# SHDN-CURRENT-S06-V00-5kWSimulation.net
KiCad netlist of a schematic drawn in Altium Designer
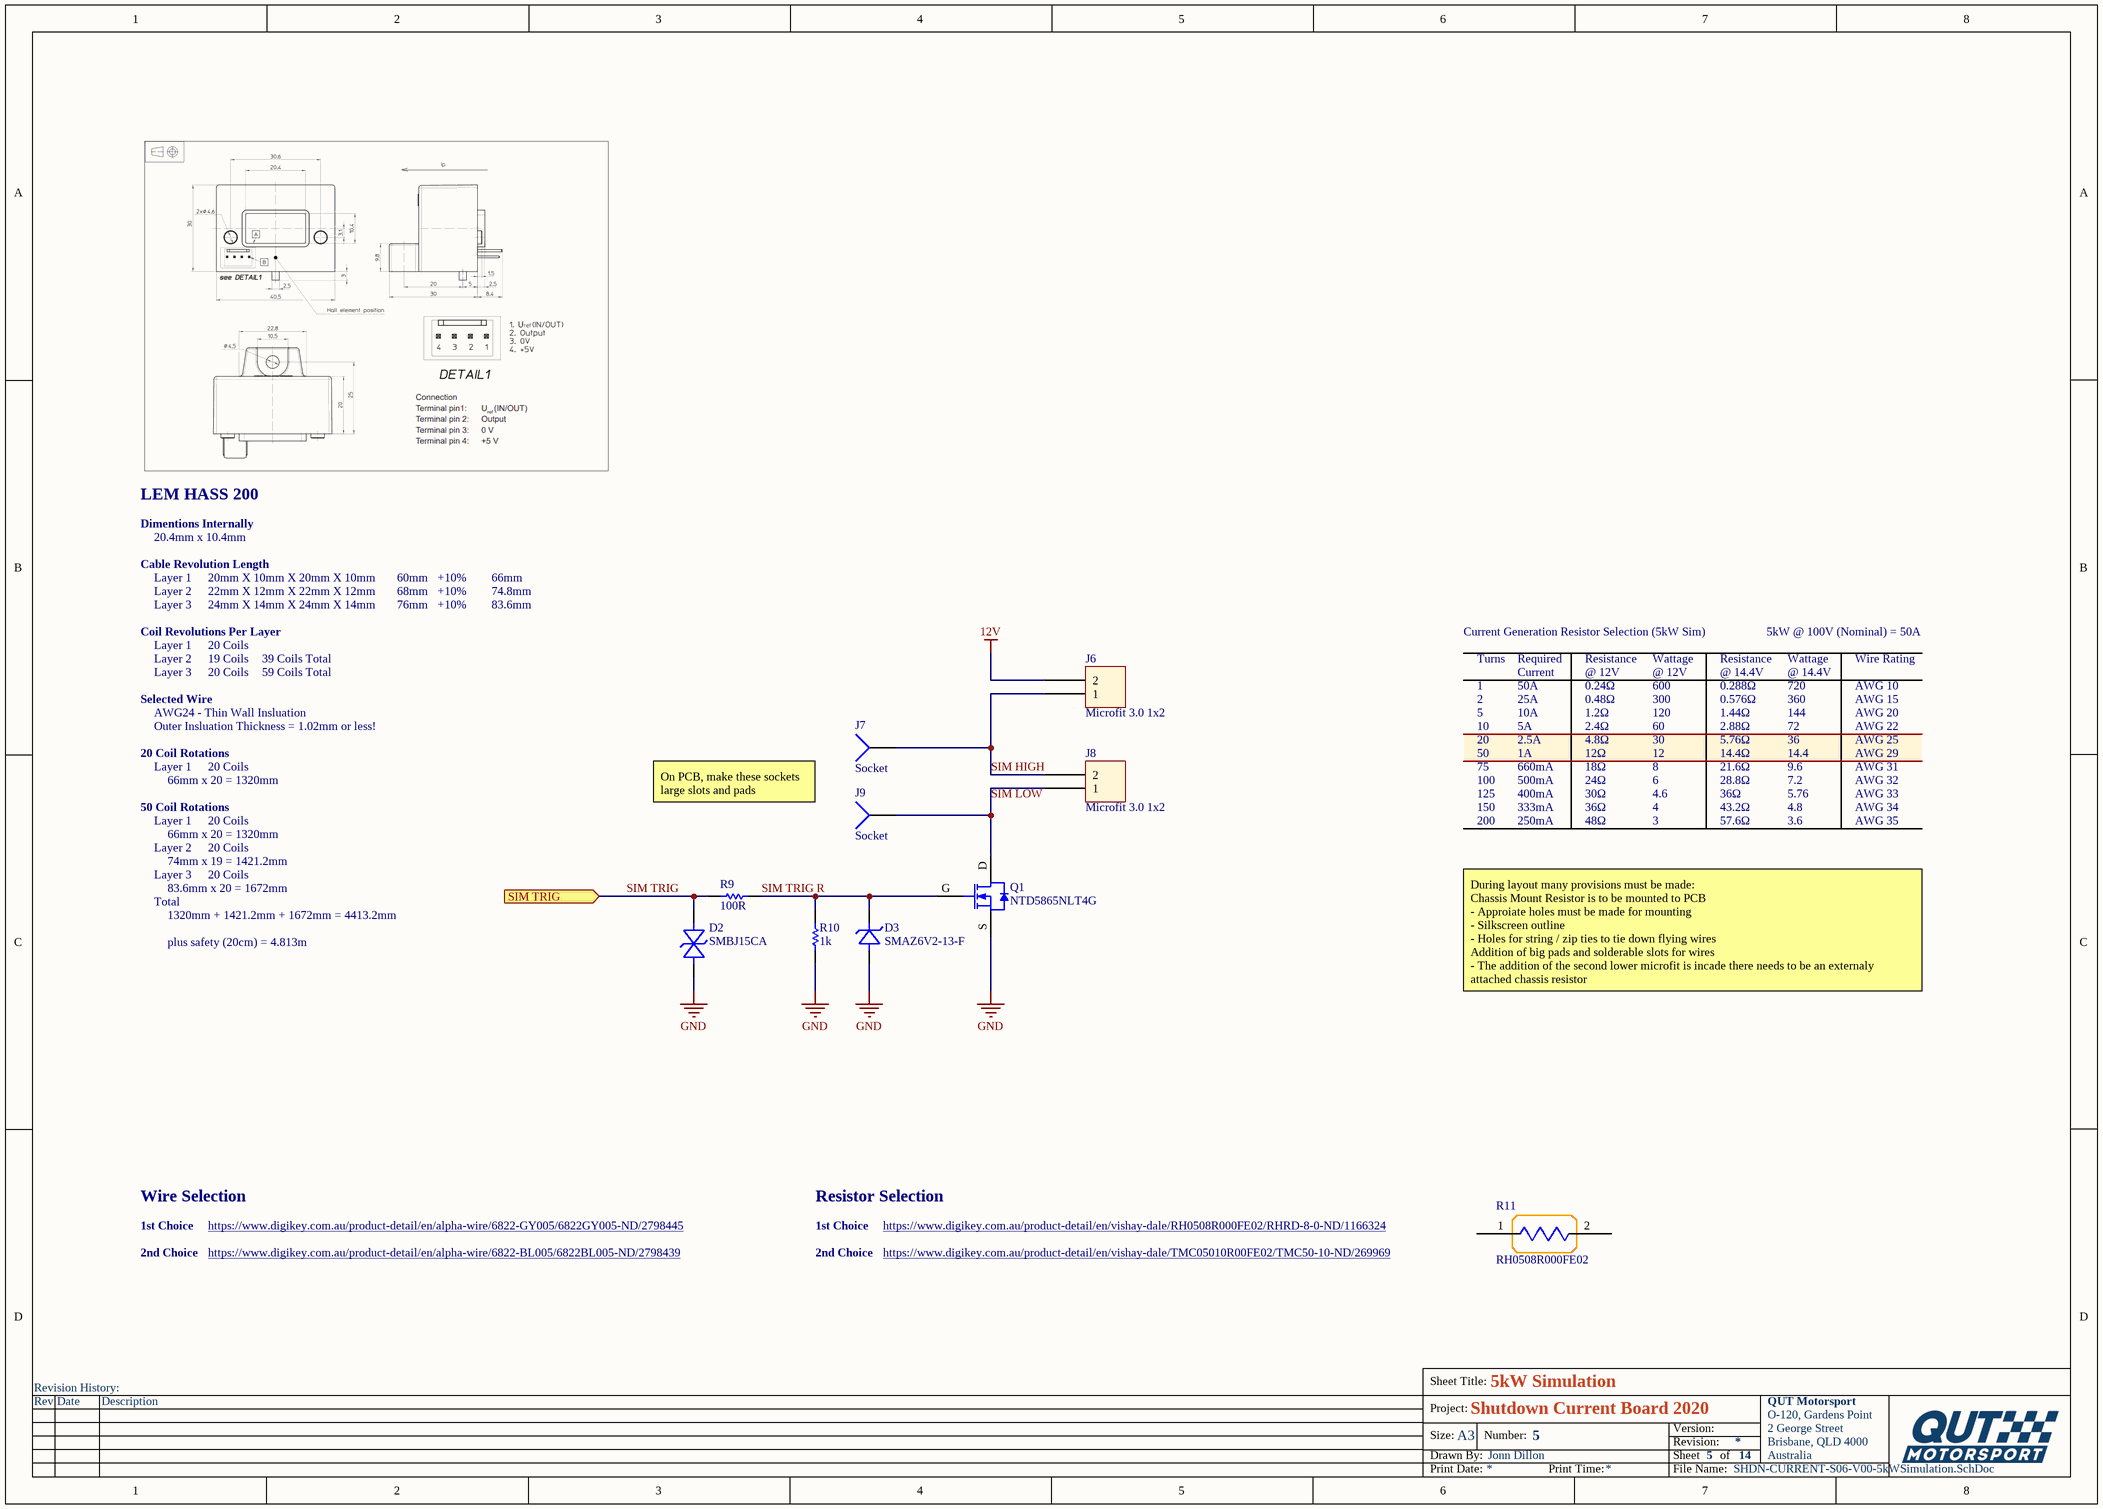
[diagram p0: SHDN-CURRENT-S06-V00-5kWSimulation.SchDoc]

(export (version "E")
  (design (tool "Eeschema 10.0.6"))
  (components
    (comp (ref "D2")
      (value "SMBJ15CA")
      (footprint "SMB")
      (description "Diode, SMD, TVS Diode, 15V 24.4V, DO214AA/SMB")
      (libsource (lib "QUTMS_DiodeLibrary") (part "SMBJ15CA"))
    )
    (comp (ref "D3")
      (value "SMAZ6V2-13-F")
      (footprint "SMA")
      (description "Zener Diode 6.2V 1W ±5% Surface Mount SMA")
      (fields (field (name "MANUFACTURER") "Generic") (field (name "MPN") "5V6 500mW SMA"))
      (libsource (lib "QUTMS_DiodeLibrary") (part "SMAZ6V2-13-F"))
    )
    (comp (ref "J6")
      (value "Microfit 3.0 1x2")
      (footprint "Microfit_1X2_R_TH")
      (libsource (lib "QUTMS_MicrofitLibrary") (part "Microfit_1x2"))
    )
    (comp (ref "J7")
      (value "Socket")
      (footprint "PIN1")
      (fields (field (name "PUBLISHER") "Altium Limited"))
      (libsource (lib "Miscellaneous Connectors") (part "Socket"))
    )
    (comp (ref "J8")
      (value "Microfit 3.0 1x2")
      (footprint "Microfit_1X2_R_TH")
      (libsource (lib "QUTMS_MicrofitLibrary") (part "Microfit_1x2"))
    )
    (comp (ref "J9")
      (value "Socket")
      (footprint "PIN1")
      (fields (field (name "PUBLISHER") "Altium Limited"))
      (libsource (lib "Miscellaneous Connectors") (part "Socket"))
    )
    (comp (ref "Q1")
      (value "NTD5865NLT4G")
      (footprint "DPAK TO-252")
      (description "NTD5865NLT4G, 60V 46A")
      (libsource (lib "QUTMS_MOSFETLibrary") (part "NTD5865NLT4G"))
    )
    (comp (ref "R9")
      (value "100R")
      (footprint "Res_ThinFilm_0603")
      (description "Resistor, SMD, 100R, 0.1W, 5%, 0603")
      (libsource (lib "StandardResistors") (part "100R 5%, 0603"))
    )
    (comp (ref "R10")
      (value "1k")
      (footprint "Res_ThinFilm_0603")
      (description "Resistor, SMD, 1k, 0.1W, 5%, 0603")
      (libsource (lib "StandardResistors") (part "1k 5% 0603"))
    )
    (comp (ref "R11")
      (value "RH0508R000FE02")
      (footprint "RH0508R000FE02")
      (description "8 Ohms ±1% 50W Wirewound Chassis Mount Resistor")
      (libsource (lib "QUTMS_SpecialResistors") (part "RH0508R000FE02"))
    )
  )
  (nets
    (net (code "1") (name "/SIM HIGH") (class "Default")
      (node (ref "J6") (pin "1") (pinfunction "1_1") (pintype "passive"))
      (node (ref "J7") (pin "1") (pinfunction "1_1") (pintype "passive"))
      (node (ref "J8") (pin "2") (pinfunction "2_2") (pintype "passive"))
    )
    (net (code "2") (name "/SIM LOW") (class "Default")
      (node (ref "J8") (pin "1") (pinfunction "1_1") (pintype "passive"))
      (node (ref "J9") (pin "1") (pinfunction "1_1") (pintype "passive"))
      (node (ref "Q1") (pin "D") (pinfunction "D_D") (pintype "passive"))
    )
    (net (code "3") (name "/SIM TRIG") (class "Default")
      (node (ref "D2") (pin "K") (pinfunction "Cathode_K") (pintype "passive"))
      (node (ref "R9") (pin "1") (pinfunction "1_1") (pintype "passive"))
    )
    (net (code "4") (name "/SIM TRIG R") (class "Default")
      (node (ref "D3") (pin "K") (pinfunction "Cathode_K") (pintype "passive"))
      (node (ref "Q1") (pin "G") (pinfunction "G_G") (pintype "passive"))
      (node (ref "R10") (pin "2") (pinfunction "2_2") (pintype "passive"))
      (node (ref "R9") (pin "2") (pinfunction "2_2") (pintype "passive"))
    )
    (net (code "5") (name "12V") (class "Default")
      (node (ref "J6") (pin "2") (pinfunction "2_2") (pintype "passive"))
    )
    (net (code "6") (name "GND") (class "Default")
      (node (ref "D2") (pin "A") (pinfunction "Anode_A") (pintype "passive"))
      (node (ref "D3") (pin "A") (pinfunction "Anode_A") (pintype "passive"))
      (node (ref "Q1") (pin "S") (pinfunction "S_S") (pintype "passive"))
      (node (ref "R10") (pin "1") (pinfunction "1_1") (pintype "passive"))
    )
    (net (code "7") (name "unconnected-(R11-Pad1)") (class "Default")
      (node (ref "R11") (pin "1") (pinfunction "1_1") (pintype "passive"))
    )
    (net (code "8") (name "unconnected-(R11-Pad2)") (class "Default")
      (node (ref "R11") (pin "2") (pinfunction "2_2") (pintype "passive"))
    )
  )
)
